# BEE222V3.net
KiCad netlist of a schematic drawn in EAGLE
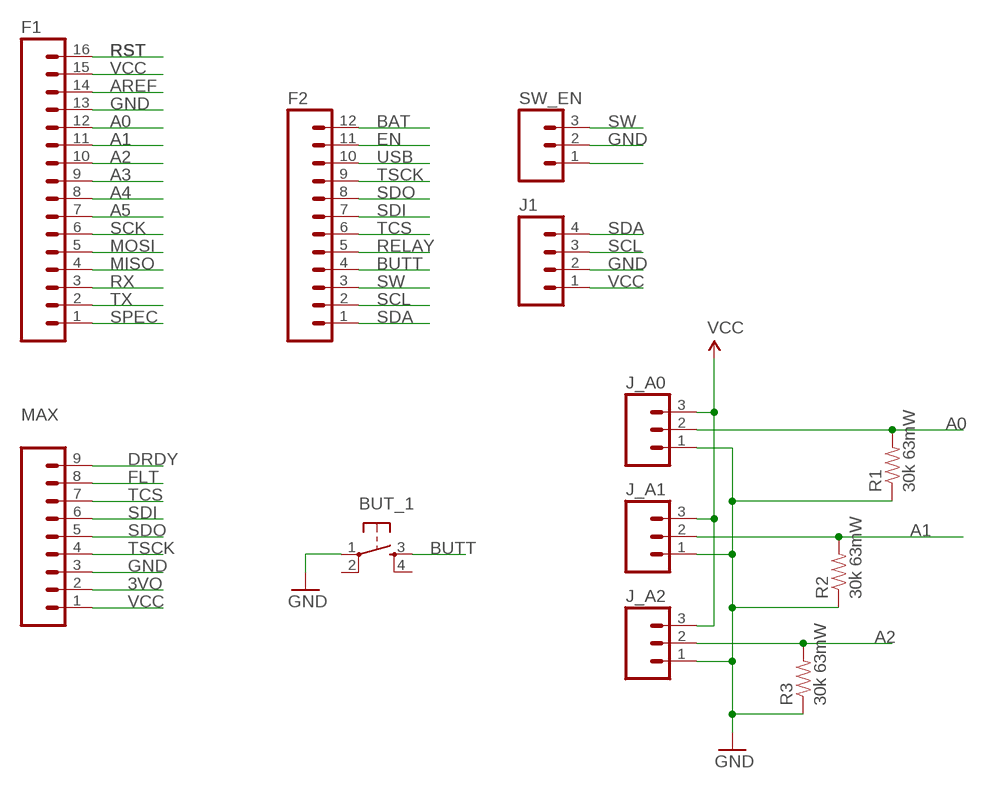
[diagram p0: schematic, sheet 1]

(export (version "E")
  (design (tool "Eeschema 10.0.6"))
  (components
    (comp (ref "BUT_1")
      (value "TAC_SWITCHPTH")
      (footprint "eagle-import:TACTILE-PTH")
      (libsource (lib "eagle-import") (part "TAC_SWITCHPTH"))
    )
    (comp (ref "F1")
      (value "M16PTH")
      (footprint "eagle-import:1X16")
      (libsource (lib "eagle-import") (part "M16PTH"))
    )
    (comp (ref "F2")
      (value "M12PTH")
      (footprint "eagle-import:1X12")
      (libsource (lib "eagle-import") (part "M12PTH"))
    )
    (comp (ref "J1")
      (value "M04PTH")
      (footprint "eagle-import:1X04")
      (libsource (lib "eagle-import") (part "M04PTH"))
    )
    (comp (ref "J_A0")
      (value "M03JST-PTH-VERT")
      (footprint "eagle-import:JST-3-PTH-VERT")
      (libsource (lib "eagle-import") (part "M03JST-PTH-VERT"))
    )
    (comp (ref "J_A1")
      (value "M03JST-PTH-VERT")
      (footprint "eagle-import:JST-3-PTH-VERT")
      (libsource (lib "eagle-import") (part "M03JST-PTH-VERT"))
    )
    (comp (ref "J_A2")
      (value "M03JST-PTH-VERT")
      (footprint "eagle-import:JST-3-PTH-VERT")
      (libsource (lib "eagle-import") (part "M03JST-PTH-VERT"))
    )
    (comp (ref "MAX")
      (value "M09")
      (footprint "eagle-import:1X09")
      (libsource (lib "eagle-import") (part "M09"))
    )
    (comp (ref "R1")
      (value "30k 63mW")
      (footprint "eagle-import:1206")
      (libsource (lib "eagle-import") (part "RESISTOR1206"))
    )
    (comp (ref "R2")
      (value "30k 63mW")
      (footprint "eagle-import:1206")
      (libsource (lib "eagle-import") (part "RESISTOR1206"))
    )
    (comp (ref "R3")
      (value "30k 63mW")
      (footprint "eagle-import:1206")
      (libsource (lib "eagle-import") (part "RESISTOR1206"))
    )
    (comp (ref "SW_EN")
      (value "M03PTH")
      (footprint "eagle-import:1X03")
      (libsource (lib "eagle-import") (part "M03PTH"))
    )
  )
  (nets
    (net (code "1") (name "/3VO") (class "Default")
      (node (ref "MAX") (pin "2") (pinfunction "2_2") (pintype "passive"))
    )
    (net (code "2") (name "/A0") (class "Default")
      (node (ref "F1") (pin "12") (pinfunction "12_12") (pintype "passive"))
      (node (ref "J_A0") (pin "2") (pinfunction "2_2") (pintype "passive"))
      (node (ref "R1") (pin "2") (pinfunction "2_2") (pintype "passive"))
    )
    (net (code "3") (name "/A1") (class "Default")
      (node (ref "F1") (pin "11") (pinfunction "11_11") (pintype "passive"))
      (node (ref "J_A1") (pin "2") (pinfunction "2_2") (pintype "passive"))
      (node (ref "R2") (pin "2") (pinfunction "2_2") (pintype "passive"))
    )
    (net (code "4") (name "/A2") (class "Default")
      (node (ref "F1") (pin "10") (pinfunction "10_10") (pintype "passive"))
      (node (ref "J_A2") (pin "2") (pinfunction "2_2") (pintype "passive"))
      (node (ref "R3") (pin "2") (pinfunction "2_2") (pintype "passive"))
    )
    (net (code "5") (name "/A3") (class "Default")
      (node (ref "F1") (pin "9") (pinfunction "9_9") (pintype "passive"))
    )
    (net (code "6") (name "/A4") (class "Default")
      (node (ref "F1") (pin "8") (pinfunction "8_8") (pintype "passive"))
    )
    (net (code "7") (name "/A5") (class "Default")
      (node (ref "F1") (pin "7") (pinfunction "7_7") (pintype "passive"))
    )
    (net (code "8") (name "/AREF") (class "Default")
      (node (ref "F1") (pin "14") (pinfunction "14_14") (pintype "passive"))
    )
    (net (code "9") (name "/BAT") (class "Default")
      (node (ref "F2") (pin "12") (pinfunction "12_12") (pintype "passive"))
    )
    (net (code "10") (name "/BUTT") (class "Default")
      (node (ref "BUT_1") (pin "3") (pinfunction "3_3") (pintype "passive"))
      (node (ref "F2") (pin "4") (pinfunction "4_4") (pintype "passive"))
    )
    (net (code "11") (name "/DRDY") (class "Default")
      (node (ref "MAX") (pin "9") (pinfunction "9_9") (pintype "passive"))
    )
    (net (code "12") (name "/EN") (class "Default")
      (node (ref "F2") (pin "11") (pinfunction "11_11") (pintype "passive"))
    )
    (net (code "13") (name "/FLT") (class "Default")
      (node (ref "MAX") (pin "8") (pinfunction "8_8") (pintype "passive"))
    )
    (net (code "14") (name "/MISO") (class "Default")
      (node (ref "F1") (pin "4") (pinfunction "4_4") (pintype "passive"))
    )
    (net (code "15") (name "/MOSI") (class "Default")
      (node (ref "F1") (pin "5") (pinfunction "5_5") (pintype "passive"))
    )
    (net (code "16") (name "/RELAY") (class "Default")
      (node (ref "F2") (pin "5") (pinfunction "5_5") (pintype "passive"))
    )
    (net (code "17") (name "/RST") (class "Default")
      (node (ref "F1") (pin "16") (pinfunction "16_16") (pintype "passive"))
    )
    (net (code "18") (name "/RX") (class "Default")
      (node (ref "F1") (pin "3") (pinfunction "3_3") (pintype "passive"))
    )
    (net (code "19") (name "/SCK") (class "Default")
      (node (ref "F1") (pin "6") (pinfunction "6_6") (pintype "passive"))
    )
    (net (code "20") (name "/SCL") (class "Default")
      (node (ref "F2") (pin "2") (pinfunction "2_2") (pintype "passive"))
      (node (ref "J1") (pin "3") (pinfunction "3_3") (pintype "passive"))
    )
    (net (code "21") (name "/SDA") (class "Default")
      (node (ref "F2") (pin "1") (pinfunction "1_1") (pintype "passive"))
      (node (ref "J1") (pin "4") (pinfunction "4_4") (pintype "passive"))
    )
    (net (code "22") (name "/SDI") (class "Default")
      (node (ref "F2") (pin "7") (pinfunction "7_7") (pintype "passive"))
      (node (ref "MAX") (pin "6") (pinfunction "6_6") (pintype "passive"))
    )
    (net (code "23") (name "/SDO") (class "Default")
      (node (ref "F2") (pin "8") (pinfunction "8_8") (pintype "passive"))
      (node (ref "MAX") (pin "5") (pinfunction "5_5") (pintype "passive"))
    )
    (net (code "24") (name "/SPEC") (class "Default")
      (node (ref "F1") (pin "1") (pinfunction "1_1") (pintype "passive"))
    )
    (net (code "25") (name "/SW") (class "Default")
      (node (ref "F2") (pin "3") (pinfunction "3_3") (pintype "passive"))
      (node (ref "SW_EN") (pin "3") (pinfunction "3_3") (pintype "passive"))
    )
    (net (code "26") (name "/TCS") (class "Default")
      (node (ref "F2") (pin "6") (pinfunction "6_6") (pintype "passive"))
      (node (ref "MAX") (pin "7") (pinfunction "7_7") (pintype "passive"))
    )
    (net (code "27") (name "/TSCK") (class "Default")
      (node (ref "F2") (pin "9") (pinfunction "9_9") (pintype "passive"))
      (node (ref "MAX") (pin "4") (pinfunction "4_4") (pintype "passive"))
    )
    (net (code "28") (name "/TX") (class "Default")
      (node (ref "F1") (pin "2") (pinfunction "2_2") (pintype "passive"))
    )
    (net (code "29") (name "/USB") (class "Default")
      (node (ref "F2") (pin "10") (pinfunction "10_10") (pintype "passive"))
    )
    (net (code "30") (name "GND") (class "Default")
      (node (ref "BUT_1") (pin "1") (pinfunction "1_1") (pintype "passive"))
      (node (ref "F1") (pin "13") (pinfunction "13_13") (pintype "passive"))
      (node (ref "J1") (pin "2") (pinfunction "2_2") (pintype "passive"))
      (node (ref "J_A0") (pin "1") (pinfunction "1_1") (pintype "passive"))
      (node (ref "J_A1") (pin "1") (pinfunction "1_1") (pintype "passive"))
      (node (ref "J_A2") (pin "1") (pinfunction "1_1") (pintype "passive"))
      (node (ref "MAX") (pin "3") (pinfunction "3_3") (pintype "passive"))
      (node (ref "R1") (pin "1") (pinfunction "1_1") (pintype "passive"))
      (node (ref "R2") (pin "1") (pinfunction "1_1") (pintype "passive"))
      (node (ref "R3") (pin "1") (pinfunction "1_1") (pintype "passive"))
      (node (ref "SW_EN") (pin "2") (pinfunction "2_2") (pintype "passive"))
    )
    (net (code "31") (name "VCC") (class "Default")
      (node (ref "F1") (pin "15") (pinfunction "15_15") (pintype "passive"))
      (node (ref "J1") (pin "1") (pinfunction "1_1") (pintype "passive"))
      (node (ref "J_A0") (pin "3") (pinfunction "3_3") (pintype "passive"))
      (node (ref "J_A1") (pin "3") (pinfunction "3_3") (pintype "passive"))
      (node (ref "J_A2") (pin "3") (pinfunction "3_3") (pintype "passive"))
      (node (ref "MAX") (pin "1") (pinfunction "1_1") (pintype "passive"))
    )
    (net (code "32") (name "unconnected-(BUT_1-Pad2)") (class "Default")
      (node (ref "BUT_1") (pin "2") (pinfunction "2_2") (pintype "passive"))
    )
    (net (code "33") (name "unconnected-(BUT_1-Pad4)") (class "Default")
      (node (ref "BUT_1") (pin "4") (pinfunction "4_4") (pintype "passive"))
    )
    (net (code "34") (name "unconnected-(SW_EN-Pad1)") (class "Default")
      (node (ref "SW_EN") (pin "1") (pinfunction "1_1") (pintype "passive"))
    )
  )
)
